# XBeeLight.net
KiCad netlist of a schematic drawn in Altium Designer
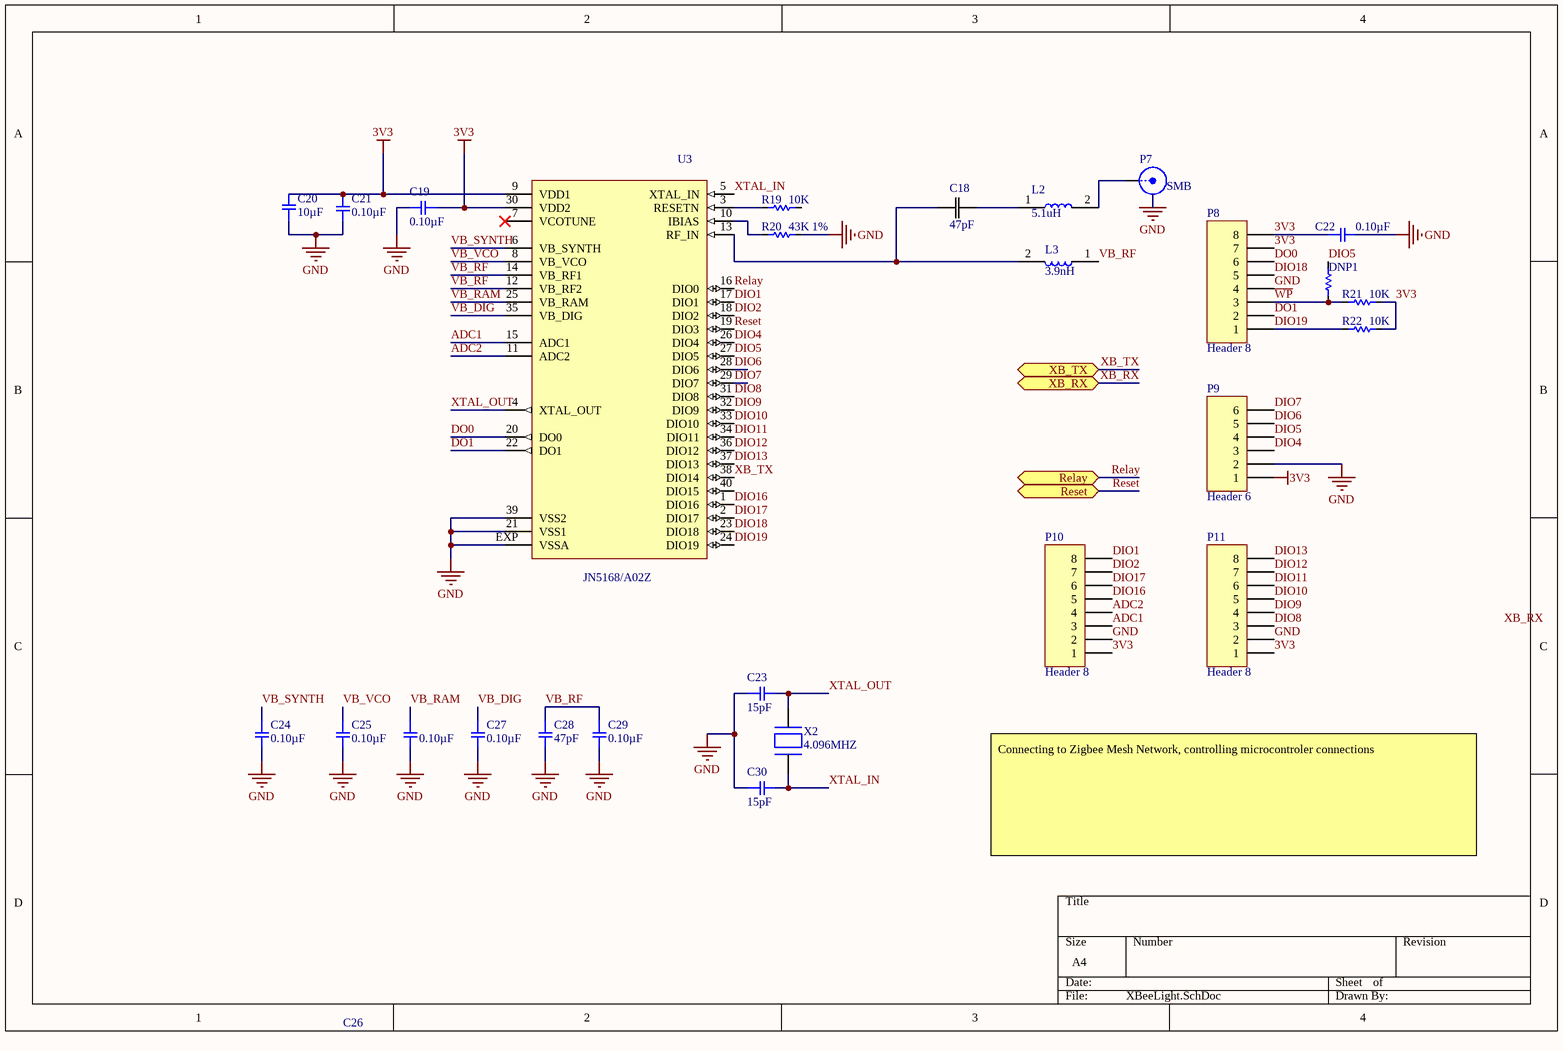
[diagram p0: XBeeLight.SchDoc]

(export (version "E")
  (design (tool "Eeschema 10.0.6"))
  (components
    (comp (ref "C18")
      (value "47pF")
      (footprint "CC0402N")
      (description "Imported")
      (fields (field (name "MANUFACTURER_PART_NUMBER") "CC0402JRNPO9BN470"))
      (libsource (lib "XBeeLight") (part "CC0402JRNPO9BN47"))
    )
    (comp (ref "C19")
      (value "0.10µF")
      (footprint "SMD-0402C")
      (description "CAP CER 0.1UF 16V X7R 0402")
      (fields
        (field (name "DIGI-KEY PART NUMBER") "490-4759-1-ND")
        (field (name "PART NUMBER") "GCM155R71C104KA55D")
      )
      (libsource (lib "Capacitors") (part "GCM155R71C104KA55D"))
    )
    (comp (ref "C20")
      (value "10µF")
      (footprint "SMD-0603C")
      (description "CAP CER 10UF 6.3V X5R 0603")
      (fields
        (field (name "DIGI-KEY PART NUMBER") "490-12538-1-ND")
        (field (name "PART NUMBER") "GRM188R60J106KE47D")
      )
      (libsource (lib "Capacitors") (part "GRM188R60J106KE47D"))
    )
    (comp (ref "C21")
      (value "0.10µF")
      (footprint "SMD-0402C")
      (description "CAP CER 0.1UF 16V X7R 0402")
      (fields
        (field (name "DIGI-KEY PART NUMBER") "490-4759-1-ND")
        (field (name "PART NUMBER") "GCM155R71C104KA55D")
      )
      (libsource (lib "Capacitors") (part "GCM155R71C104KA55D"))
    )
    (comp (ref "C22")
      (value "0.10µF")
      (footprint "SMD-0402C")
      (description "CAP CER 0.1UF 16V X7R 0402")
      (fields
        (field (name "DIGI-KEY PART NUMBER") "490-4759-1-ND")
        (field (name "PART NUMBER") "GCM155R71C104KA55D")
      )
      (libsource (lib "Capacitors") (part "GCM155R71C104KA55D"))
    )
    (comp (ref "C23")
      (value "15pF")
      (footprint "SMD-0402C")
      (description "CAP CER 15PF 50V NP0 0402")
      (fields
        (field (name "DIGI-KEY PART NUMBER") "490-11191-1-ND")
        (field (name "PART NUMBER") "GJM1555C1H150FB01D")
      )
      (libsource (lib "Capacitors") (part "GJM1555C1H150FB01D"))
    )
    (comp (ref "C24")
      (value "0.10µF")
      (footprint "SMD-0402C")
      (description "CAP CER 0.1UF 16V X7R 0402")
      (fields
        (field (name "DIGI-KEY PART NUMBER") "490-4759-1-ND")
        (field (name "PART NUMBER") "GCM155R71C104KA55D")
      )
      (libsource (lib "Capacitors") (part "GCM155R71C104KA55D"))
    )
    (comp (ref "C25")
      (value "0.10µF")
      (footprint "SMD-0402C")
      (description "CAP CER 0.1UF 16V X7R 0402")
      (fields
        (field (name "DIGI-KEY PART NUMBER") "490-4759-1-ND")
        (field (name "PART NUMBER") "GCM155R71C104KA55D")
      )
      (libsource (lib "Capacitors") (part "GCM155R71C104KA55D"))
    )
    (comp (ref "C26")
      (value "0.10µF")
      (footprint "SMD-0402C")
      (description "CAP CER 0.1UF 16V X7R 0402")
      (fields
        (field (name "DIGI-KEY PART NUMBER") "490-4759-1-ND")
        (field (name "PART NUMBER") "GCM155R71C104KA55D")
      )
      (libsource (lib "Capacitors") (part "GCM155R71C104KA55D"))
    )
    (comp (ref "C27")
      (value "0.10µF")
      (footprint "SMD-0402C")
      (description "CAP CER 0.1UF 16V X7R 0402")
      (fields
        (field (name "DIGI-KEY PART NUMBER") "490-4759-1-ND")
        (field (name "PART NUMBER") "GCM155R71C104KA55D")
      )
      (libsource (lib "Capacitors") (part "GCM155R71C104KA55D"))
    )
    (comp (ref "C28")
      (value "47pF")
      (footprint "SMD-0402C")
      (description "CAP CER 47PF 50V NP0 0402")
      (fields
        (field (name "DIGI-KEY PART NUMBER") "490-10670-1-ND")
        (field (name "PART NUMBER") "GCM1555C1H470JA16D")
      )
      (libsource (lib "Capacitors") (part "GCM1555C1H470JA16D"))
    )
    (comp (ref "C29")
      (value "0.10µF")
      (footprint "SMD-0402C")
      (description "CAP CER 0.1UF 16V X7R 0402")
      (fields
        (field (name "DIGI-KEY PART NUMBER") "490-4759-1-ND")
        (field (name "PART NUMBER") "GCM155R71C104KA55D")
      )
      (libsource (lib "Capacitors") (part "GCM155R71C104KA55D"))
    )
    (comp (ref "C30")
      (value "15pF")
      (footprint "SMD-0402C")
      (description "CAP CER 15PF 50V NP0 0402")
      (fields
        (field (name "DIGI-KEY PART NUMBER") "490-11191-1-ND")
        (field (name "PART NUMBER") "GJM1555C1H150FB01D")
      )
      (libsource (lib "Capacitors") (part "GJM1555C1H150FB01D"))
    )
    (comp (ref "DNP1")
      (value "10K")
      (footprint "MCS 0402")
      (description "Res Thin Film 0402 10K Ohm 0.5% 0.063W(1/16W) ±25ppm/C Molded SMD Automotive Punched T/R")
      (fields
        (field (name "MANUFACTURER") "Panasonic")
        (field (name "MANUFACTURER PART NUMBER") "ERA-2AED103X")
      )
      (libsource (lib "XBeeLight") (part "10K Res"))
    )
    (comp (ref "L2")
      (value "5.1uH")
      (footprint "INDC1005X45")
      (fields
        (field (name "MF") "Murata")
        (field (name "DIGI-KEY_PART_NUMBER") "490-6758-1-ND")
        (field (name "MP") "LQP15MN5N1B02D")
      )
      (libsource (lib "XBeeLight") (part "LQP15MN5N1B02D"))
    )
    (comp (ref "L3")
      (value "3.9nH")
      (footprint "INDC1005X45")
      (description "FIXED IND 3.9NH 170MA 500 MOHM")
      (fields
        (field (name "MANUFACTURER") "Murata")
        (field (name "MANUFACTURER PART NUMBER") "LQP15MN3N9B02D")
      )
      (libsource (lib "XBeeLight") (part "LQP15MN3N9B02D"))
    )
    (comp (ref "P7")
      (value "SMB")
      (footprint "SMB_V-RJ45")
      (description "SMB Straight Connector")
      (fields (field (name "PUBLISHER") "Altium Limited"))
      (libsource (lib "Miscellaneous Connectors") (part "SMB"))
    )
    (comp (ref "P8")
      (value "Header 8")
      (footprint "HDR1X8")
      (description "Header, 8-Pin")
      (fields (field (name "PUBLISHER") "Altium Limited"))
      (libsource (lib "Miscellaneous Connectors") (part "Header 8"))
    )
    (comp (ref "P9")
      (value "Header 6")
      (footprint "HDR1X6")
      (description "Header, 6-Pin")
      (fields (field (name "PUBLISHER") "Altium Limited"))
      (libsource (lib "Miscellaneous Connectors") (part "Header 6"))
    )
    (comp (ref "P10")
      (value "Header 8")
      (footprint "HDR1X8")
      (description "Header, 8-Pin")
      (fields (field (name "PUBLISHER") "Altium Limited"))
      (libsource (lib "Miscellaneous Connectors") (part "Header 8"))
    )
    (comp (ref "P11")
      (value "Header 8")
      (footprint "HDR1X8")
      (description "Header, 8-Pin")
      (fields (field (name "PUBLISHER") "Altium Limited"))
      (libsource (lib "Miscellaneous Connectors") (part "Header 8"))
    )
    (comp (ref "R19")
      (value "10K")
      (footprint "MCS 0402")
      (description "Res Thin Film 0402 10K Ohm 0.5% 0.063W(1/16W) ±25ppm/C Molded SMD Automotive Punched T/R")
      (fields
        (field (name "MANUFACTURER") "Panasonic")
        (field (name "MANUFACTURER PART NUMBER") "ERA-2AED103X")
      )
      (libsource (lib "XBeeLight") (part "10K Res"))
    )
    (comp (ref "R20")
      (value "43K 1%")
      (footprint "RC0402N")
      (description "Imported")
      (fields (field (name "MANUFACTURER_PART_NUMBER") "ERJ-2RKF4302X"))
      (libsource (lib "XBeeLight") (part "Res 43K"))
    )
    (comp (ref "R21")
      (value "10K")
      (footprint "MCS 0402")
      (description "Res Thin Film 0402 10K Ohm 0.5% 0.063W(1/16W) ±25ppm/C Molded SMD Automotive Punched T/R")
      (fields
        (field (name "MANUFACTURER") "Panasonic")
        (field (name "MANUFACTURER PART NUMBER") "ERA-2AED103X")
      )
      (libsource (lib "XBeeLight") (part "10K Res"))
    )
    (comp (ref "R22")
      (value "10K")
      (footprint "MCS 0402")
      (description "Res Thin Film 0402 10K Ohm 0.5% 0.063W(1/16W) ±25ppm/C Molded SMD Automotive Punched T/R")
      (fields
        (field (name "MANUFACTURER") "Panasonic")
        (field (name "MANUFACTURER PART NUMBER") "ERA-2AED103X")
      )
      (libsource (lib "XBeeLight") (part "10K Res"))
    )
    (comp (ref "U3")
      (value "JN5168/A02Z")
      (footprint "QFN50P600X600X100-41N_JN5168/A02Z(Primary)")
      (fields (field (name "MF") "NXP Semiconductors"))
      (libsource (lib "XBeeLight") (part "JN5168/A02Z"))
    )
    (comp (ref "X2")
      (value "4.096MHZ")
      (footprint "XTAL_ABLS2-4.096MHZ-D4Y-T")
      (description "4.096MHz ±30ppm Crystal 18pF 180 Ohm -40°C ~ 85°C  Surface Mount HC49/US")
      (fields
        (field (name "MANUFACTURER") "Abracon")
        (field (name "MANUFACTURER PART NUMBER") "ABLS2-4.096MHZ-D4Y-T")
      )
      (libsource (lib "XBeeLight") (part "ABLS2-4.096MHZ-D4Y-T"))
    )
  )
  (nets
    (net (code "1") (name "/ADC1") (class "Default")
      (node (ref "P10") (pin "3") (pinfunction "3_3") (pintype "passive"))
      (node (ref "U3") (pin "15") (pinfunction "ADC1_15") (pintype "power_in"))
    )
    (net (code "2") (name "/ADC2") (class "Default")
      (node (ref "P10") (pin "4") (pinfunction "4_4") (pintype "passive"))
      (node (ref "U3") (pin "11") (pinfunction "ADC2_11") (pintype "power_in"))
    )
    (net (code "3") (name "/DIO1") (class "Default")
      (node (ref "P10") (pin "8") (pinfunction "8_8") (pintype "passive"))
      (node (ref "U3") (pin "17") (pinfunction "DIO1_17") (pintype "bidirectional"))
    )
    (net (code "4") (name "/DIO2") (class "Default")
      (node (ref "P10") (pin "7") (pinfunction "7_7") (pintype "passive"))
      (node (ref "U3") (pin "18") (pinfunction "DIO2_18") (pintype "bidirectional"))
    )
    (net (code "5") (name "/DIO4") (class "Default")
      (node (ref "P9") (pin "3") (pinfunction "3_3") (pintype "passive"))
      (node (ref "U3") (pin "26") (pinfunction "DIO4_26") (pintype "bidirectional"))
    )
    (net (code "6") (name "/DIO5") (class "Default")
      (node (ref "DNP1") (pin "2") (pinfunction "2_2") (pintype "passive"))
      (node (ref "P9") (pin "4") (pinfunction "4_4") (pintype "passive"))
      (node (ref "U3") (pin "27") (pinfunction "DIO5_27") (pintype "bidirectional"))
    )
    (net (code "7") (name "/DIO6") (class "Default")
      (node (ref "P9") (pin "5") (pinfunction "5_5") (pintype "passive"))
      (node (ref "U3") (pin "28") (pinfunction "DIO6_28") (pintype "bidirectional"))
    )
    (net (code "8") (name "/DIO7") (class "Default")
      (node (ref "P9") (pin "6") (pinfunction "6_6") (pintype "passive"))
      (node (ref "U3") (pin "29") (pinfunction "DIO7_29") (pintype "bidirectional"))
    )
    (net (code "9") (name "/DIO8") (class "Default")
      (node (ref "P11") (pin "3") (pinfunction "3_3") (pintype "passive"))
      (node (ref "U3") (pin "31") (pinfunction "DIO8_31") (pintype "bidirectional"))
    )
    (net (code "10") (name "/DIO9") (class "Default")
      (node (ref "P11") (pin "4") (pinfunction "4_4") (pintype "passive"))
      (node (ref "U3") (pin "32") (pinfunction "DIO9_32") (pintype "bidirectional"))
    )
    (net (code "11") (name "/DIO10") (class "Default")
      (node (ref "P11") (pin "5") (pinfunction "5_5") (pintype "passive"))
      (node (ref "U3") (pin "33") (pinfunction "DIO10_33") (pintype "bidirectional"))
    )
    (net (code "12") (name "/DIO11") (class "Default")
      (node (ref "P11") (pin "6") (pinfunction "6_6") (pintype "passive"))
      (node (ref "U3") (pin "34") (pinfunction "DIO11_34") (pintype "bidirectional"))
    )
    (net (code "13") (name "/DIO12") (class "Default")
      (node (ref "P11") (pin "7") (pinfunction "7_7") (pintype "passive"))
      (node (ref "U3") (pin "36") (pinfunction "DIO12_36") (pintype "bidirectional"))
    )
    (net (code "14") (name "/DIO13") (class "Default")
      (node (ref "P11") (pin "8") (pinfunction "8_8") (pintype "passive"))
      (node (ref "U3") (pin "37") (pinfunction "DIO13_37") (pintype "bidirectional"))
    )
    (net (code "15") (name "/DIO16") (class "Default")
      (node (ref "P10") (pin "5") (pinfunction "5_5") (pintype "passive"))
      (node (ref "U3") (pin "1") (pinfunction "DIO16_1") (pintype "bidirectional"))
    )
    (net (code "16") (name "/DIO17") (class "Default")
      (node (ref "P10") (pin "6") (pinfunction "6_6") (pintype "passive"))
      (node (ref "U3") (pin "2") (pinfunction "DIO17_2") (pintype "bidirectional"))
    )
    (net (code "17") (name "/DIO18") (class "Default")
      (node (ref "P8") (pin "5") (pinfunction "5_5") (pintype "passive"))
      (node (ref "U3") (pin "23") (pinfunction "DIO18_23") (pintype "bidirectional"))
    )
    (net (code "18") (name "/DIO19") (class "Default")
      (node (ref "P8") (pin "1") (pinfunction "1_1") (pintype "passive"))
      (node (ref "R22") (pin "1") (pinfunction "1_1") (pintype "passive"))
      (node (ref "U3") (pin "24") (pinfunction "DIO19_24") (pintype "bidirectional"))
    )
    (net (code "19") (name "/DO0") (class "Default")
      (node (ref "P8") (pin "6") (pinfunction "6_6") (pintype "passive"))
      (node (ref "U3") (pin "20") (pinfunction "DO0_20") (pintype "output"))
    )
    (net (code "20") (name "/DO1") (class "Default")
      (node (ref "P8") (pin "2") (pinfunction "2_2") (pintype "passive"))
      (node (ref "U3") (pin "22") (pinfunction "DO1_22") (pintype "output"))
    )
    (net (code "21") (name "/Relay") (class "Default")
      (node (ref "U3") (pin "16") (pinfunction "DIO0_16") (pintype "bidirectional"))
    )
    (net (code "22") (name "/Reset") (class "Default")
      (node (ref "U3") (pin "19") (pinfunction "DIO3_19") (pintype "bidirectional"))
    )
    (net (code "23") (name "/VB_DIG") (class "Default")
      (node (ref "C27") (pin "1") (pinfunction "1_1") (pintype "passive"))
      (node (ref "U3") (pin "35") (pinfunction "VB_DIG_35") (pintype "power_in"))
    )
    (net (code "24") (name "/VB_RAM") (class "Default")
      (node (ref "C26") (pin "1") (pinfunction "1_1") (pintype "passive"))
      (node (ref "U3") (pin "25") (pinfunction "VB_RAM_25") (pintype "power_in"))
    )
    (net (code "25") (name "/VB_RF") (class "Default")
      (node (ref "C28") (pin "1") (pinfunction "1_1") (pintype "passive"))
      (node (ref "C29") (pin "1") (pinfunction "1_1") (pintype "passive"))
      (node (ref "L3") (pin "1") (pinfunction "1_1") (pintype "passive"))
      (node (ref "U3") (pin "12") (pinfunction "VB_RF2_12") (pintype "power_in"))
      (node (ref "U3") (pin "14") (pinfunction "VB_RF1_14") (pintype "power_in"))
    )
    (net (code "26") (name "/VB_SYNTH") (class "Default")
      (node (ref "C24") (pin "1") (pinfunction "1_1") (pintype "passive"))
      (node (ref "U3") (pin "6") (pinfunction "VB_SYNTH_6") (pintype "power_in"))
    )
    (net (code "27") (name "/VB_VCO") (class "Default")
      (node (ref "C25") (pin "1") (pinfunction "1_1") (pintype "passive"))
      (node (ref "U3") (pin "8") (pinfunction "VB_VCO_8") (pintype "power_in"))
    )
    (net (code "29") (name "/XB_TX") (class "Default")
      (node (ref "U3") (pin "38") (pinfunction "DIO14_38") (pintype "bidirectional"))
    )
    (net (code "30") (name "/XTAL_IN") (class "Default")
      (node (ref "C30") (pin "2") (pinfunction "2_2") (pintype "passive"))
      (node (ref "U3") (pin "5") (pinfunction "XTAL_IN_5") (pintype "input"))
      (node (ref "X2") (pin "1") (pinfunction "1_1") (pintype "passive"))
    )
    (net (code "31") (name "/XTAL_OUT") (class "Default")
      (node (ref "C23") (pin "2") (pinfunction "2_2") (pintype "passive"))
      (node (ref "U3") (pin "4") (pinfunction "XTAL_OUT_4") (pintype "output"))
      (node (ref "X2") (pin "2") (pinfunction "2_2") (pintype "passive"))
    )
    (net (code "32") (name "/~{WP}") (class "Default")
      (node (ref "DNP1") (pin "1") (pinfunction "1_1") (pintype "passive"))
      (node (ref "P8") (pin "3") (pinfunction "3_3") (pintype "passive"))
      (node (ref "R21") (pin "1") (pinfunction "1_1") (pintype "passive"))
    )
    (net (code "33") (name "3V3") (class "Default")
      (node (ref "C19") (pin "1") (pinfunction "1_1") (pintype "passive"))
      (node (ref "C20") (pin "2") (pinfunction "2_2") (pintype "passive"))
      (node (ref "C21") (pin "1") (pinfunction "1_1") (pintype "passive"))
      (node (ref "C22") (pin "1") (pinfunction "1_1") (pintype "passive"))
      (node (ref "P10") (pin "1") (pinfunction "1_1") (pintype "passive"))
      (node (ref "P11") (pin "1") (pinfunction "1_1") (pintype "passive"))
      (node (ref "P8") (pin "7") (pinfunction "7_7") (pintype "passive"))
      (node (ref "P8") (pin "8") (pinfunction "8_8") (pintype "passive"))
      (node (ref "P9") (pin "1") (pinfunction "1_1") (pintype "passive"))
      (node (ref "R21") (pin "2") (pinfunction "2_2") (pintype "passive"))
      (node (ref "R22") (pin "2") (pinfunction "2_2") (pintype "passive"))
      (node (ref "U3") (pin "30") (pinfunction "VDD2_30") (pintype "power_in"))
      (node (ref "U3") (pin "9") (pinfunction "VDD1_9") (pintype "power_in"))
    )
    (net (code "34") (name "GND") (class "Default")
      (node (ref "C19") (pin "2") (pinfunction "2_2") (pintype "passive"))
      (node (ref "C20") (pin "1") (pinfunction "1_1") (pintype "passive"))
      (node (ref "C21") (pin "2") (pinfunction "2_2") (pintype "passive"))
      (node (ref "C22") (pin "2") (pinfunction "2_2") (pintype "passive"))
      (node (ref "C23") (pin "1") (pinfunction "1_1") (pintype "passive"))
      (node (ref "C24") (pin "2") (pinfunction "2_2") (pintype "passive"))
      (node (ref "C25") (pin "2") (pinfunction "2_2") (pintype "passive"))
      (node (ref "C26") (pin "2") (pinfunction "2_2") (pintype "passive"))
      (node (ref "C27") (pin "2") (pinfunction "2_2") (pintype "passive"))
      (node (ref "C28") (pin "2") (pinfunction "2_2") (pintype "passive"))
      (node (ref "C29") (pin "2") (pinfunction "2_2") (pintype "passive"))
      (node (ref "C30") (pin "1") (pinfunction "1_1") (pintype "passive"))
      (node (ref "P10") (pin "2") (pinfunction "2_2") (pintype "passive"))
      (node (ref "P11") (pin "2") (pinfunction "2_2") (pintype "passive"))
      (node (ref "P7") (pin "2") (pinfunction "Y_2") (pintype "passive"))
      (node (ref "P8") (pin "4") (pinfunction "4_4") (pintype "passive"))
      (node (ref "P9") (pin "2") (pinfunction "2_2") (pintype "passive"))
      (node (ref "R20") (pin "2") (pinfunction "2_2") (pintype "passive"))
      (node (ref "U3") (pin "21") (pinfunction "VSS1_21") (pintype "power_in"))
      (node (ref "U3") (pin "39") (pinfunction "VSS2_39") (pintype "power_in"))
      (node (ref "U3") (pin "EXP") (pinfunction "VSSA_EXP") (pintype "power_in"))
    )
    (net (code "35") (name "Net-(C18-Pad1)") (class "Default")
      (node (ref "C18") (pin "1") (pinfunction "1_1") (pintype "passive"))
      (node (ref "L2") (pin "1") (pinfunction "1_1") (pintype "passive"))
    )
    (net (code "36") (name "Net-(P7-X)") (class "Default")
      (node (ref "L2") (pin "2") (pinfunction "2_2") (pintype "passive"))
      (node (ref "P7") (pin "1") (pinfunction "X_1") (pintype "passive"))
    )
    (net (code "37") (name "Net-(U3-IBIAS)") (class "Default")
      (node (ref "R20") (pin "1") (pinfunction "1_1") (pintype "passive"))
      (node (ref "U3") (pin "10") (pinfunction "IBIAS_10") (pintype "input"))
    )
    (net (code "38") (name "Net-(U3-RESETN)") (class "Default")
      (node (ref "R19") (pin "1") (pinfunction "1_1") (pintype "passive"))
      (node (ref "U3") (pin "3") (pinfunction "RESETN_3") (pintype "input"))
    )
    (net (code "39") (name "Net-(U3-RF_IN)") (class "Default")
      (node (ref "C18") (pin "2") (pinfunction "2_2") (pintype "passive"))
      (node (ref "L3") (pin "2") (pinfunction "2_2") (pintype "passive"))
      (node (ref "U3") (pin "13") (pinfunction "RF_IN_13") (pintype "input"))
    )
    (net (code "40") (name "unconnected-(R19-Pad2)") (class "Default")
      (node (ref "R19") (pin "2") (pinfunction "2_2") (pintype "passive"))
    )
    (net (code "41") (name "unconnected-(U3-DIO15-Pad40)") (class "Default")
      (node (ref "U3") (pin "40") (pinfunction "DIO15_40") (pintype "bidirectional"))
    )
    (net (code "42") (name "unconnected-(U3-VCOTUNE-Pad7)") (class "Default")
      (node (ref "U3") (pin "7") (pinfunction "VCOTUNE_7") (pintype "power_in+no_connect"))
    )
  )
)
